# rock-climbing-timer.net
KiCad netlist of a schematic drawn in EAGLE
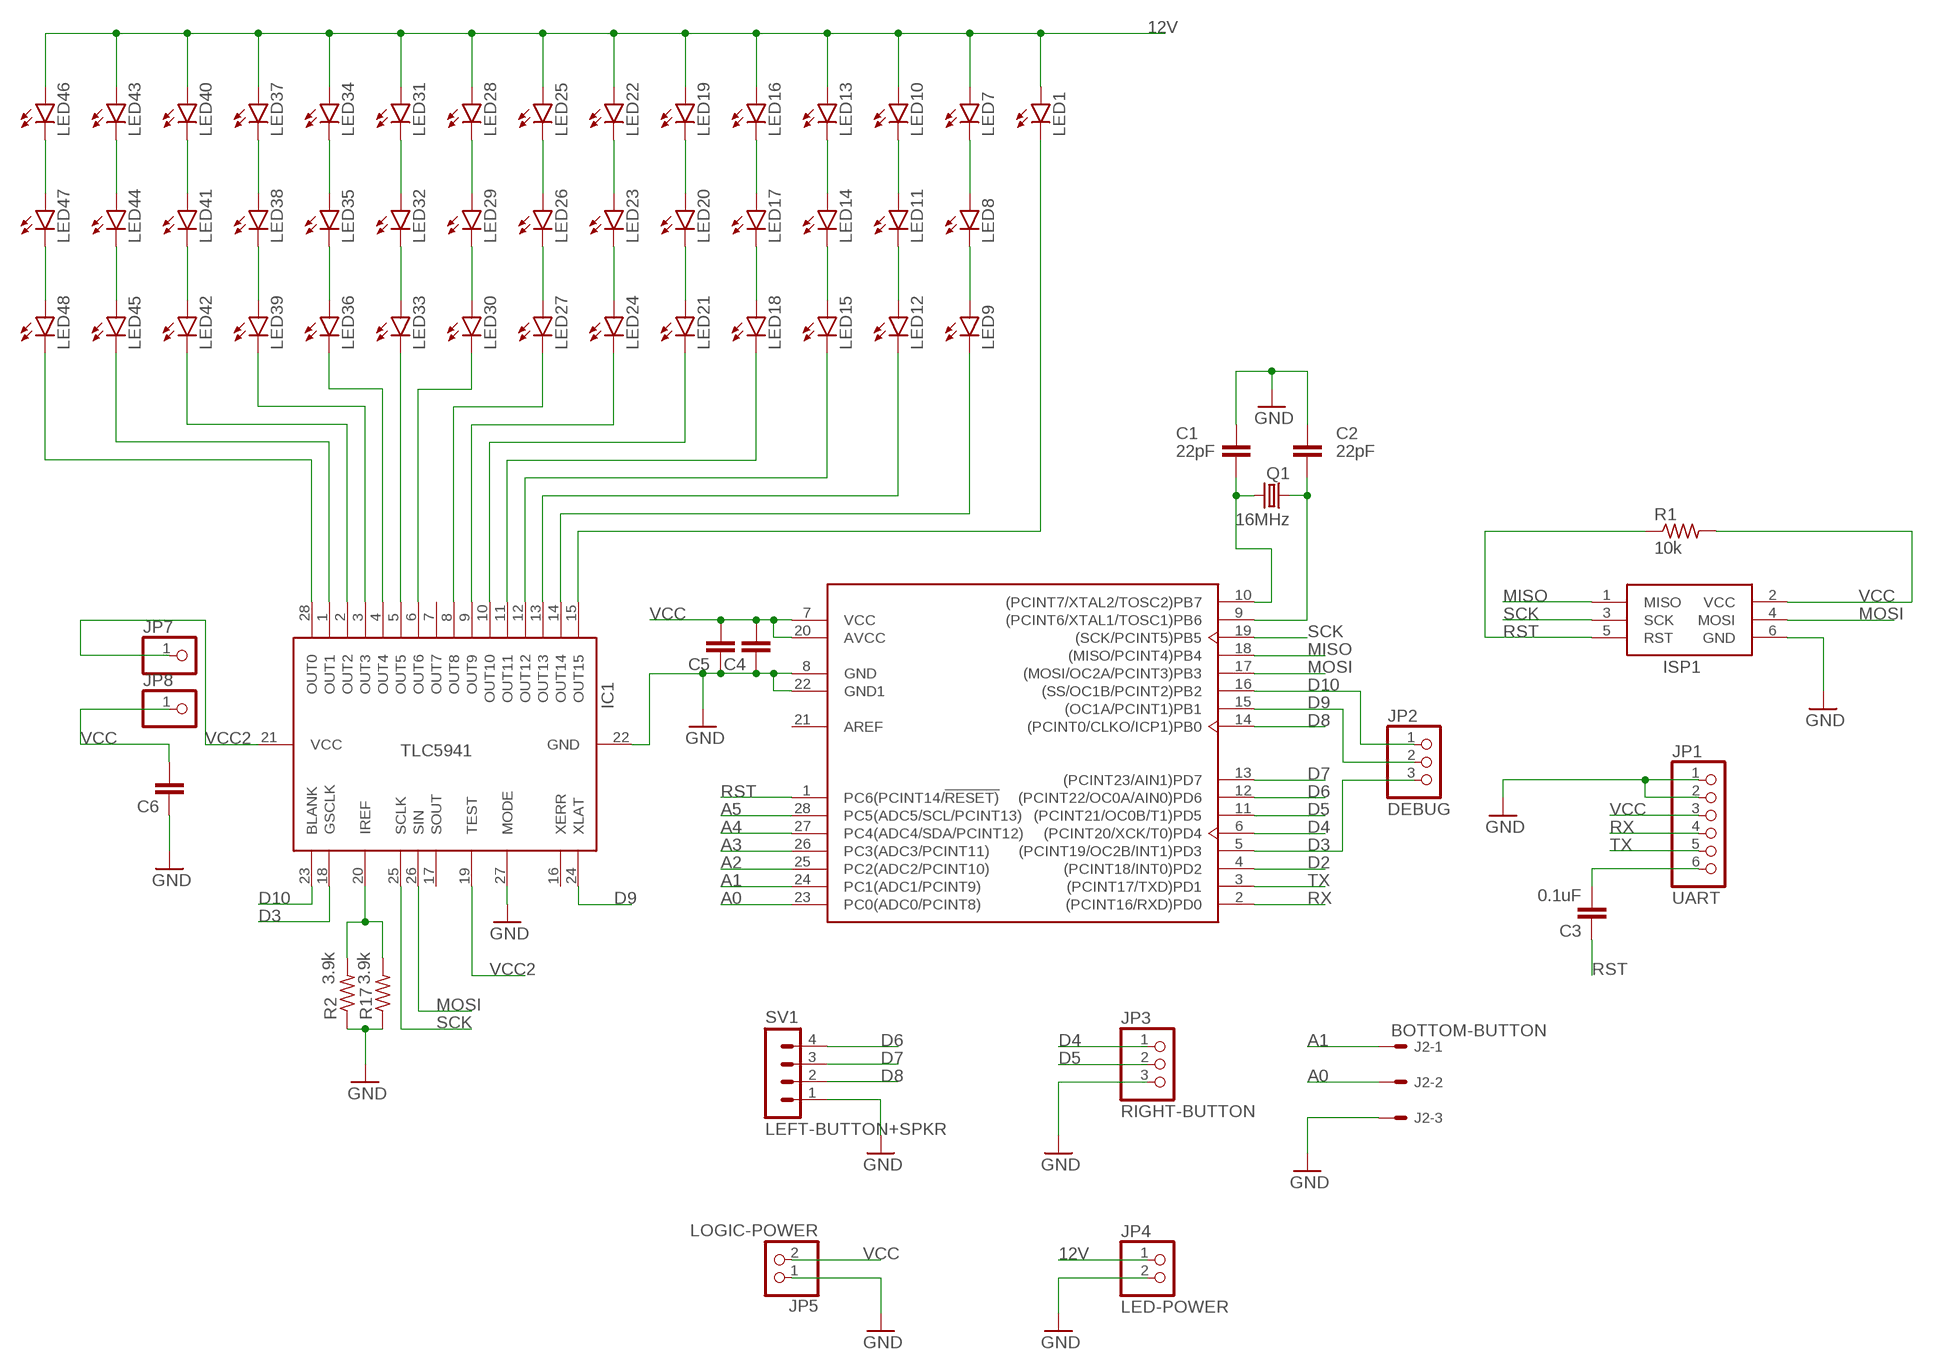
[diagram p0: schematic, sheet 1]

(export (version "E")
  (design (tool "Eeschema 10.0.6"))
  (components
    (comp (ref "C1")
      (value "22pF")
      (footprint "eagle-import:C5B2.5")
      (libsource (lib "eagle-import") (part "C5/2.5"))
    )
    (comp (ref "C2")
      (value "22pF")
      (footprint "eagle-import:C5B2.5")
      (libsource (lib "eagle-import") (part "C5/2.5"))
    )
    (comp (ref "C3")
      (value "0.1uF")
      (footprint "eagle-import:C5B2.5")
      (libsource (lib "eagle-import") (part "C5/2.5"))
    )
    (comp (ref "C4")
      (value "C5/2.5")
      (footprint "eagle-import:C5B2.5")
      (libsource (lib "eagle-import") (part "C5/2.5"))
    )
    (comp (ref "C5")
      (value "C5/2.5")
      (footprint "eagle-import:C5B2.5")
      (libsource (lib "eagle-import") (part "C5/2.5"))
    )
    (comp (ref "C6")
      (value "C5/2.5")
      (footprint "eagle-import:C5B2.5")
      (libsource (lib "eagle-import") (part "C5/2.5"))
    )
    (comp (ref "IC1")
      (value "TLC5941NT")
      (footprint "eagle-import:DIL28-3")
      (libsource (lib "eagle-import") (part "TLC5941NT"))
    )
    (comp (ref "ISP1")
      (value "AVRISP-6")
      (footprint "eagle-import:AVRISP")
      (libsource (lib "eagle-import") (part "AVRISP-6"))
    )
    (comp (ref "J2")
      (value "BOTTOM-BUTTON")
      (footprint "eagle-import:6410-03")
      (fields (field (name "MF") "MOLEX"))
      (libsource (lib "eagle-import") (part "22-?-0327-2031"))
    )
    (comp (ref "JP1")
      (value "UART")
      (footprint "eagle-import:1X06")
      (libsource (lib "eagle-import") (part "PINHD-1X6"))
    )
    (comp (ref "JP2")
      (value "DEBUG")
      (footprint "eagle-import:1X03")
      (libsource (lib "eagle-import") (part "PINHD-1X3"))
    )
    (comp (ref "JP3")
      (value "RIGHT-BUTTON")
      (footprint "eagle-import:1X03")
      (libsource (lib "eagle-import") (part "PINHD-1X3"))
    )
    (comp (ref "JP4")
      (value "LED-POWER")
      (footprint "eagle-import:1X02")
      (libsource (lib "eagle-import") (part "PINHD-1X2"))
    )
    (comp (ref "JP5")
      (value "LOGIC-POWER")
      (footprint "eagle-import:1X02")
      (libsource (lib "eagle-import") (part "PINHD-1X2"))
    )
    (comp (ref "JP7")
      (value "PINHD-1X1CB")
      (footprint "eagle-import:1X01-CLEANBIG")
      (libsource (lib "eagle-import") (part "PINHD-1X1CB"))
    )
    (comp (ref "JP8")
      (value "PINHD-1X1CB")
      (footprint "eagle-import:1X01-CLEANBIG")
      (libsource (lib "eagle-import") (part "PINHD-1X1CB"))
    )
    (comp (ref "LED1")
      (value "LED5MM")
      (footprint "eagle-import:LED5MM")
      (libsource (lib "eagle-import") (part "LED5MM"))
    )
    (comp (ref "LED7")
      (value "LED5MM")
      (footprint "eagle-import:LED5MM")
      (libsource (lib "eagle-import") (part "LED5MM"))
    )
    (comp (ref "LED8")
      (value "LED5MM")
      (footprint "eagle-import:LED5MM")
      (libsource (lib "eagle-import") (part "LED5MM"))
    )
    (comp (ref "LED9")
      (value "LED5MM")
      (footprint "eagle-import:LED5MM")
      (libsource (lib "eagle-import") (part "LED5MM"))
    )
    (comp (ref "LED10")
      (value "LED5MM")
      (footprint "eagle-import:LED5MM")
      (libsource (lib "eagle-import") (part "LED5MM"))
    )
    (comp (ref "LED11")
      (value "LED5MM")
      (footprint "eagle-import:LED5MM")
      (libsource (lib "eagle-import") (part "LED5MM"))
    )
    (comp (ref "LED12")
      (value "LED5MM")
      (footprint "eagle-import:LED5MM")
      (libsource (lib "eagle-import") (part "LED5MM"))
    )
    (comp (ref "LED13")
      (value "LED5MM")
      (footprint "eagle-import:LED5MM")
      (libsource (lib "eagle-import") (part "LED5MM"))
    )
    (comp (ref "LED14")
      (value "LED5MM")
      (footprint "eagle-import:LED5MM")
      (libsource (lib "eagle-import") (part "LED5MM"))
    )
    (comp (ref "LED15")
      (value "LED5MM")
      (footprint "eagle-import:LED5MM")
      (libsource (lib "eagle-import") (part "LED5MM"))
    )
    (comp (ref "LED16")
      (value "LED5MM")
      (footprint "eagle-import:LED5MM")
      (libsource (lib "eagle-import") (part "LED5MM"))
    )
    (comp (ref "LED17")
      (value "LED5MM")
      (footprint "eagle-import:LED5MM")
      (libsource (lib "eagle-import") (part "LED5MM"))
    )
    (comp (ref "LED18")
      (value "LED5MM")
      (footprint "eagle-import:LED5MM")
      (libsource (lib "eagle-import") (part "LED5MM"))
    )
    (comp (ref "LED19")
      (value "LED5MM")
      (footprint "eagle-import:LED5MM")
      (libsource (lib "eagle-import") (part "LED5MM"))
    )
    (comp (ref "LED20")
      (value "LED5MM")
      (footprint "eagle-import:LED5MM")
      (libsource (lib "eagle-import") (part "LED5MM"))
    )
    (comp (ref "LED21")
      (value "LED5MM")
      (footprint "eagle-import:LED5MM")
      (libsource (lib "eagle-import") (part "LED5MM"))
    )
    (comp (ref "LED22")
      (value "LED5MM")
      (footprint "eagle-import:LED5MM")
      (libsource (lib "eagle-import") (part "LED5MM"))
    )
    (comp (ref "LED23")
      (value "LED5MM")
      (footprint "eagle-import:LED5MM")
      (libsource (lib "eagle-import") (part "LED5MM"))
    )
    (comp (ref "LED24")
      (value "LED5MM")
      (footprint "eagle-import:LED5MM")
      (libsource (lib "eagle-import") (part "LED5MM"))
    )
    (comp (ref "LED25")
      (value "LED5MM")
      (footprint "eagle-import:LED5MM")
      (libsource (lib "eagle-import") (part "LED5MM"))
    )
    (comp (ref "LED26")
      (value "LED5MM")
      (footprint "eagle-import:LED5MM")
      (libsource (lib "eagle-import") (part "LED5MM"))
    )
    (comp (ref "LED27")
      (value "LED5MM")
      (footprint "eagle-import:LED5MM")
      (libsource (lib "eagle-import") (part "LED5MM"))
    )
    (comp (ref "LED28")
      (value "LED5MM")
      (footprint "eagle-import:LED5MM")
      (libsource (lib "eagle-import") (part "LED5MM"))
    )
    (comp (ref "LED29")
      (value "LED5MM")
      (footprint "eagle-import:LED5MM")
      (libsource (lib "eagle-import") (part "LED5MM"))
    )
    (comp (ref "LED30")
      (value "LED5MM")
      (footprint "eagle-import:LED5MM")
      (libsource (lib "eagle-import") (part "LED5MM"))
    )
    (comp (ref "LED31")
      (value "LED5MM")
      (footprint "eagle-import:LED5MM")
      (libsource (lib "eagle-import") (part "LED5MM"))
    )
    (comp (ref "LED32")
      (value "LED5MM")
      (footprint "eagle-import:LED5MM")
      (libsource (lib "eagle-import") (part "LED5MM"))
    )
    (comp (ref "LED33")
      (value "LED5MM")
      (footprint "eagle-import:LED5MM")
      (libsource (lib "eagle-import") (part "LED5MM"))
    )
    (comp (ref "LED34")
      (value "LED5MM")
      (footprint "eagle-import:LED5MM")
      (libsource (lib "eagle-import") (part "LED5MM"))
    )
    (comp (ref "LED35")
      (value "LED5MM")
      (footprint "eagle-import:LED5MM")
      (libsource (lib "eagle-import") (part "LED5MM"))
    )
    (comp (ref "LED36")
      (value "LED5MM")
      (footprint "eagle-import:LED5MM")
      (libsource (lib "eagle-import") (part "LED5MM"))
    )
    (comp (ref "LED37")
      (value "LED5MM")
      (footprint "eagle-import:LED5MM")
      (libsource (lib "eagle-import") (part "LED5MM"))
    )
    (comp (ref "LED38")
      (value "LED5MM")
      (footprint "eagle-import:LED5MM")
      (libsource (lib "eagle-import") (part "LED5MM"))
    )
    (comp (ref "LED39")
      (value "LED5MM")
      (footprint "eagle-import:LED5MM")
      (libsource (lib "eagle-import") (part "LED5MM"))
    )
    (comp (ref "LED40")
      (value "LED5MM")
      (footprint "eagle-import:LED5MM")
      (libsource (lib "eagle-import") (part "LED5MM"))
    )
    (comp (ref "LED41")
      (value "LED5MM")
      (footprint "eagle-import:LED5MM")
      (libsource (lib "eagle-import") (part "LED5MM"))
    )
    (comp (ref "LED42")
      (value "LED5MM")
      (footprint "eagle-import:LED5MM")
      (libsource (lib "eagle-import") (part "LED5MM"))
    )
    (comp (ref "LED43")
      (value "LED5MM")
      (footprint "eagle-import:LED5MM")
      (libsource (lib "eagle-import") (part "LED5MM"))
    )
    (comp (ref "LED44")
      (value "LED5MM")
      (footprint "eagle-import:LED5MM")
      (libsource (lib "eagle-import") (part "LED5MM"))
    )
    (comp (ref "LED45")
      (value "LED5MM")
      (footprint "eagle-import:LED5MM")
      (libsource (lib "eagle-import") (part "LED5MM"))
    )
    (comp (ref "LED46")
      (value "LED5MM")
      (footprint "eagle-import:LED5MM")
      (libsource (lib "eagle-import") (part "LED5MM"))
    )
    (comp (ref "LED47")
      (value "LED5MM")
      (footprint "eagle-import:LED5MM")
      (libsource (lib "eagle-import") (part "LED5MM"))
    )
    (comp (ref "LED48")
      (value "LED5MM")
      (footprint "eagle-import:LED5MM")
      (libsource (lib "eagle-import") (part "LED5MM"))
    )
    (comp (ref "Q1")
      (value "16MHz")
      (footprint "eagle-import:HC49_S")
      (libsource (lib "eagle-import") (part "CRYSTALHC49S"))
    )
    (comp (ref "R1")
      (value "10k")
      (footprint "eagle-import:0207_10")
      (libsource (lib "eagle-import") (part "R-US_0207/10"))
    )
    (comp (ref "R2")
      (value "3.9k")
      (footprint "eagle-import:0207_10")
      (libsource (lib "eagle-import") (part "R-US_0207/10"))
    )
    (comp (ref "R17")
      (value "3.9k")
      (footprint "eagle-import:0207_10")
      (libsource (lib "eagle-import") (part "R-US_0207/10"))
    )
    (comp (ref "SV1")
      (value "LEFT-BUTTON+SPKR")
      (footprint "eagle-import:MA04-1")
      (libsource (lib "eagle-import") (part "MA04-1"))
    )
    (comp (ref "U1")
      (value "ATMEGA328P-PU")
      (footprint "eagle-import:DIP-28")
      (fields
        (field (name "DIGIKEY_PART_NUMBER") "ATMEGA328P-PU-ND")
        (field (name "MANUFACTURER") "Microchip Technology")
        (field (name "CREATED_BY") "PCBLayout.com")
      )
      (libsource (lib "eagle-import") (part "ATMEGA328P-PU"))
    )
  )
  (nets
    (net (code "1") (name "/12V") (class "Default")
      (node (ref "JP4") (pin "1") (pinfunction "1_1") (pintype "passive"))
      (node (ref "LED1") (pin "A") (pinfunction "A_A") (pintype "passive"))
      (node (ref "LED10") (pin "A") (pinfunction "A_A") (pintype "passive"))
      (node (ref "LED13") (pin "A") (pinfunction "A_A") (pintype "passive"))
      (node (ref "LED16") (pin "A") (pinfunction "A_A") (pintype "passive"))
      (node (ref "LED19") (pin "A") (pinfunction "A_A") (pintype "passive"))
      (node (ref "LED22") (pin "A") (pinfunction "A_A") (pintype "passive"))
      (node (ref "LED25") (pin "A") (pinfunction "A_A") (pintype "passive"))
      (node (ref "LED28") (pin "A") (pinfunction "A_A") (pintype "passive"))
      (node (ref "LED31") (pin "A") (pinfunction "A_A") (pintype "passive"))
      (node (ref "LED34") (pin "A") (pinfunction "A_A") (pintype "passive"))
      (node (ref "LED37") (pin "A") (pinfunction "A_A") (pintype "passive"))
      (node (ref "LED40") (pin "A") (pinfunction "A_A") (pintype "passive"))
      (node (ref "LED43") (pin "A") (pinfunction "A_A") (pintype "passive"))
      (node (ref "LED46") (pin "A") (pinfunction "A_A") (pintype "passive"))
      (node (ref "LED7") (pin "A") (pinfunction "A_A") (pintype "passive"))
    )
    (net (code "2") (name "/A0") (class "Default")
      (node (ref "J2") (pin "2") (pinfunction "S_2") (pintype "passive"))
      (node (ref "U1") (pin "23") (pinfunction "PC0(ADC0/PCINT8)_23") (pintype "bidirectional"))
    )
    (net (code "3") (name "/A1") (class "Default")
      (node (ref "J2") (pin "1") (pinfunction "S_1") (pintype "passive"))
      (node (ref "U1") (pin "24") (pinfunction "PC1(ADC1/PCINT9)_24") (pintype "bidirectional"))
    )
    (net (code "4") (name "/A2") (class "Default")
      (node (ref "U1") (pin "25") (pinfunction "PC2(ADC2/PCINT10)_25") (pintype "bidirectional"))
    )
    (net (code "5") (name "/A3") (class "Default")
      (node (ref "U1") (pin "26") (pinfunction "PC3(ADC3/PCINT11)_26") (pintype "bidirectional"))
    )
    (net (code "6") (name "/A4") (class "Default")
      (node (ref "U1") (pin "27") (pinfunction "PC4(ADC4/SDA/PCINT12)_27") (pintype "bidirectional"))
    )
    (net (code "7") (name "/A5") (class "Default")
      (node (ref "U1") (pin "28") (pinfunction "PC5(ADC5/SCL/PCINT13)_28") (pintype "bidirectional"))
    )
    (net (code "8") (name "/D2") (class "Default")
      (node (ref "U1") (pin "4") (pinfunction "(PCINT18/INT0)PD2_4") (pintype "bidirectional"))
    )
    (net (code "9") (name "/D3") (class "Default")
      (node (ref "IC1") (pin "18") (pinfunction "GSCLK_18") (pintype "input"))
      (node (ref "JP2") (pin "3") (pinfunction "3_3") (pintype "passive"))
      (node (ref "U1") (pin "5") (pinfunction "(PCINT19/OC2B/INT1)PD3_5") (pintype "bidirectional"))
    )
    (net (code "10") (name "/D4") (class "Default")
      (node (ref "JP3") (pin "1") (pinfunction "1_1") (pintype "passive"))
      (node (ref "U1") (pin "6") (pinfunction "(PCINT20/XCK/T0)PD4_6") (pintype "bidirectional"))
    )
    (net (code "11") (name "/D5") (class "Default")
      (node (ref "JP3") (pin "2") (pinfunction "2_2") (pintype "passive"))
      (node (ref "U1") (pin "11") (pinfunction "(PCINT21/OC0B/T1)PD5_11") (pintype "bidirectional"))
    )
    (net (code "12") (name "/D6") (class "Default")
      (node (ref "SV1") (pin "4") (pinfunction "4_4") (pintype "passive"))
      (node (ref "U1") (pin "12") (pinfunction "(PCINT22/OC0A/AIN0)PD6_12") (pintype "bidirectional"))
    )
    (net (code "13") (name "/D7") (class "Default")
      (node (ref "SV1") (pin "3") (pinfunction "3_3") (pintype "passive"))
      (node (ref "U1") (pin "13") (pinfunction "(PCINT23/AIN1)PD7_13") (pintype "bidirectional"))
    )
    (net (code "14") (name "/D8") (class "Default")
      (node (ref "SV1") (pin "2") (pinfunction "2_2") (pintype "passive"))
      (node (ref "U1") (pin "14") (pinfunction "(PCINT0/CLKO/ICP1)PB0_14") (pintype "bidirectional"))
    )
    (net (code "15") (name "/D9") (class "Default")
      (node (ref "IC1") (pin "24") (pinfunction "XLAT_24") (pintype "input"))
      (node (ref "JP2") (pin "2") (pinfunction "2_2") (pintype "passive"))
      (node (ref "U1") (pin "15") (pinfunction "(OC1A/PCINT1)PB1_15") (pintype "bidirectional"))
    )
    (net (code "16") (name "/D10") (class "Default")
      (node (ref "IC1") (pin "23") (pinfunction "BLANK_23") (pintype "input"))
      (node (ref "JP2") (pin "1") (pinfunction "1_1") (pintype "passive"))
      (node (ref "U1") (pin "16") (pinfunction "(SS/OC1B/PCINT2)PB2_16") (pintype "bidirectional"))
    )
    (net (code "17") (name "/MISO") (class "Default")
      (node (ref "ISP1") (pin "1") (pinfunction "MISO_1") (pintype "input"))
      (node (ref "U1") (pin "18") (pinfunction "(MISO/PCINT4)PB4_18") (pintype "bidirectional"))
    )
    (net (code "18") (name "/MOSI") (class "Default")
      (node (ref "IC1") (pin "26") (pinfunction "SIN_26") (pintype "input"))
      (node (ref "ISP1") (pin "4") (pinfunction "MOSI_4") (pintype "output"))
      (node (ref "U1") (pin "17") (pinfunction "(MOSI/OC2A/PCINT3)PB3_17") (pintype "bidirectional"))
    )
    (net (code "19") (name "/RST") (class "Default")
      (node (ref "C3") (pin "1") (pinfunction "1_1") (pintype "passive"))
      (node (ref "ISP1") (pin "5") (pinfunction "RST_5") (pintype "output"))
      (node (ref "R1") (pin "1") (pinfunction "1_1") (pintype "passive"))
      (node (ref "U1") (pin "1") (pinfunction "PC6(PCINT14/~{RESET})_1") (pintype "bidirectional"))
    )
    (net (code "20") (name "/RX") (class "Default")
      (node (ref "JP1") (pin "4") (pinfunction "4_4") (pintype "passive"))
      (node (ref "U1") (pin "2") (pinfunction "(PCINT16/RXD)PD0_2") (pintype "bidirectional"))
    )
    (net (code "21") (name "/SCK") (class "Default")
      (node (ref "IC1") (pin "25") (pinfunction "SCLK_25") (pintype "input"))
      (node (ref "ISP1") (pin "3") (pinfunction "SCK_3") (pintype "output"))
      (node (ref "U1") (pin "19") (pinfunction "(SCK/PCINT5)PB5_19") (pintype "bidirectional"))
    )
    (net (code "22") (name "/TX") (class "Default")
      (node (ref "JP1") (pin "5") (pinfunction "5_5") (pintype "passive"))
      (node (ref "U1") (pin "3") (pinfunction "(PCINT17/TXD)PD1_3") (pintype "bidirectional"))
    )
    (net (code "23") (name "/VCC") (class "Default")
      (node (ref "C4") (pin "2") (pinfunction "2_2") (pintype "passive"))
      (node (ref "C5") (pin "2") (pinfunction "2_2") (pintype "passive"))
      (node (ref "C6") (pin "2") (pinfunction "2_2") (pintype "passive"))
      (node (ref "ISP1") (pin "2") (pinfunction "VCC_2") (pintype "power_in"))
      (node (ref "JP1") (pin "3") (pinfunction "3_3") (pintype "passive"))
      (node (ref "JP5") (pin "2") (pinfunction "2_2") (pintype "passive"))
      (node (ref "JP8") (pin "1") (pinfunction "1_1") (pintype "passive"))
      (node (ref "R1") (pin "2") (pinfunction "2_2") (pintype "passive"))
      (node (ref "U1") (pin "20") (pinfunction "AVCC_20") (pintype "power_in"))
      (node (ref "U1") (pin "7") (pinfunction "VCC_7") (pintype "power_in"))
    )
    (net (code "24") (name "/VCC2") (class "Default")
      (node (ref "IC1") (pin "19") (pinfunction "TEST_19") (pintype "input"))
      (node (ref "IC1") (pin "21") (pinfunction "VCC_21") (pintype "power_in"))
      (node (ref "JP7") (pin "1") (pinfunction "1_1") (pintype "passive"))
    )
    (net (code "25") (name "GND") (class "Default")
      (node (ref "C1") (pin "1") (pinfunction "1_1") (pintype "passive"))
      (node (ref "C2") (pin "1") (pinfunction "1_1") (pintype "passive"))
      (node (ref "C4") (pin "1") (pinfunction "1_1") (pintype "passive"))
      (node (ref "C5") (pin "1") (pinfunction "1_1") (pintype "passive"))
      (node (ref "C6") (pin "1") (pinfunction "1_1") (pintype "passive"))
      (node (ref "IC1") (pin "22") (pinfunction "GND_22") (pintype "power_in"))
      (node (ref "IC1") (pin "27") (pinfunction "MODE_27") (pintype "input"))
      (node (ref "ISP1") (pin "6") (pinfunction "GND_6") (pintype "power_in"))
      (node (ref "J2") (pin "3") (pinfunction "S_3") (pintype "passive"))
      (node (ref "JP1") (pin "1") (pinfunction "1_1") (pintype "passive"))
      (node (ref "JP1") (pin "2") (pinfunction "2_2") (pintype "passive"))
      (node (ref "JP3") (pin "3") (pinfunction "3_3") (pintype "passive"))
      (node (ref "JP4") (pin "2") (pinfunction "2_2") (pintype "passive"))
      (node (ref "JP5") (pin "1") (pinfunction "1_1") (pintype "passive"))
      (node (ref "R17") (pin "1") (pinfunction "1_1") (pintype "passive"))
      (node (ref "R2") (pin "1") (pinfunction "1_1") (pintype "passive"))
      (node (ref "SV1") (pin "1") (pinfunction "1_1") (pintype "passive"))
      (node (ref "U1") (pin "22") (pinfunction "GND1_22") (pintype "power_in"))
      (node (ref "U1") (pin "8") (pinfunction "GND_8") (pintype "power_in"))
    )
    (net (code "26") (name "Net-(C3-Pad2)") (class "Default")
      (node (ref "C3") (pin "2") (pinfunction "2_2") (pintype "passive"))
      (node (ref "JP1") (pin "6") (pinfunction "6_6") (pintype "passive"))
    )
    (net (code "27") (name "Net-(IC1-IREF)") (class "Default")
      (node (ref "IC1") (pin "20") (pinfunction "IREF_20") (pintype "bidirectional"))
      (node (ref "R17") (pin "2") (pinfunction "2_2") (pintype "passive"))
      (node (ref "R2") (pin "2") (pinfunction "2_2") (pintype "passive"))
    )
    (net (code "28") (name "Net-(IC1-OUT0)") (class "Default")
      (node (ref "IC1") (pin "28") (pinfunction "OUT0_28") (pintype "output"))
      (node (ref "LED48") (pin "K") (pinfunction "C_K") (pintype "passive"))
    )
    (net (code "29") (name "Net-(IC1-OUT1)") (class "Default")
      (node (ref "IC1") (pin "1") (pinfunction "OUT1_1") (pintype "output"))
      (node (ref "LED45") (pin "K") (pinfunction "C_K") (pintype "passive"))
    )
    (net (code "30") (name "Net-(IC1-OUT2)") (class "Default")
      (node (ref "IC1") (pin "2") (pinfunction "OUT2_2") (pintype "output"))
      (node (ref "LED42") (pin "K") (pinfunction "C_K") (pintype "passive"))
    )
    (net (code "31") (name "Net-(IC1-OUT3)") (class "Default")
      (node (ref "IC1") (pin "3") (pinfunction "OUT3_3") (pintype "output"))
      (node (ref "LED39") (pin "K") (pinfunction "C_K") (pintype "passive"))
    )
    (net (code "32") (name "Net-(IC1-OUT4)") (class "Default")
      (node (ref "IC1") (pin "4") (pinfunction "OUT4_4") (pintype "output"))
      (node (ref "LED36") (pin "K") (pinfunction "C_K") (pintype "passive"))
    )
    (net (code "33") (name "Net-(IC1-OUT5)") (class "Default")
      (node (ref "IC1") (pin "5") (pinfunction "OUT5_5") (pintype "output"))
      (node (ref "LED33") (pin "K") (pinfunction "C_K") (pintype "passive"))
    )
    (net (code "34") (name "Net-(IC1-OUT6)") (class "Default")
      (node (ref "IC1") (pin "6") (pinfunction "OUT6_6") (pintype "output"))
      (node (ref "LED30") (pin "K") (pinfunction "C_K") (pintype "passive"))
    )
    (net (code "35") (name "Net-(IC1-OUT8)") (class "Default")
      (node (ref "IC1") (pin "8") (pinfunction "OUT8_8") (pintype "output"))
      (node (ref "LED27") (pin "K") (pinfunction "C_K") (pintype "passive"))
    )
    (net (code "36") (name "Net-(IC1-OUT9)") (class "Default")
      (node (ref "IC1") (pin "9") (pinfunction "OUT9_9") (pintype "output"))
      (node (ref "LED24") (pin "K") (pinfunction "C_K") (pintype "passive"))
    )
    (net (code "37") (name "Net-(IC1-OUT10)") (class "Default")
      (node (ref "IC1") (pin "10") (pinfunction "OUT10_10") (pintype "output"))
      (node (ref "LED21") (pin "K") (pinfunction "C_K") (pintype "passive"))
    )
    (net (code "38") (name "Net-(IC1-OUT11)") (class "Default")
      (node (ref "IC1") (pin "11") (pinfunction "OUT11_11") (pintype "output"))
      (node (ref "LED18") (pin "K") (pinfunction "C_K") (pintype "passive"))
    )
    (net (code "39") (name "Net-(IC1-OUT12)") (class "Default")
      (node (ref "IC1") (pin "12") (pinfunction "OUT12_12") (pintype "output"))
      (node (ref "LED15") (pin "K") (pinfunction "C_K") (pintype "passive"))
    )
    (net (code "40") (name "Net-(IC1-OUT13)") (class "Default")
      (node (ref "IC1") (pin "13") (pinfunction "OUT13_13") (pintype "output"))
      (node (ref "LED12") (pin "K") (pinfunction "C_K") (pintype "passive"))
    )
    (net (code "41") (name "Net-(IC1-OUT14)") (class "Default")
      (node (ref "IC1") (pin "14") (pinfunction "OUT14_14") (pintype "output"))
      (node (ref "LED9") (pin "K") (pinfunction "C_K") (pintype "passive"))
    )
    (net (code "42") (name "Net-(IC1-OUT15)") (class "Default")
      (node (ref "IC1") (pin "15") (pinfunction "OUT15_15") (pintype "output"))
      (node (ref "LED1") (pin "K") (pinfunction "C_K") (pintype "passive"))
    )
    (net (code "43") (name "Net-(LED7-C)") (class "Default")
      (node (ref "LED7") (pin "K") (pinfunction "C_K") (pintype "passive"))
      (node (ref "LED8") (pin "A") (pinfunction "A_A") (pintype "passive"))
    )
    (net (code "44") (name "Net-(LED8-C)") (class "Default")
      (node (ref "LED8") (pin "K") (pinfunction "C_K") (pintype "passive"))
      (node (ref "LED9") (pin "A") (pinfunction "A_A") (pintype "passive"))
    )
    (net (code "45") (name "Net-(LED10-C)") (class "Default")
      (node (ref "LED10") (pin "K") (pinfunction "C_K") (pintype "passive"))
      (node (ref "LED11") (pin "A") (pinfunction "A_A") (pintype "passive"))
    )
    (net (code "46") (name "Net-(LED11-C)") (class "Default")
      (node (ref "LED11") (pin "K") (pinfunction "C_K") (pintype "passive"))
      (node (ref "LED12") (pin "A") (pinfunction "A_A") (pintype "passive"))
    )
    (net (code "47") (name "Net-(LED13-C)") (class "Default")
      (node (ref "LED13") (pin "K") (pinfunction "C_K") (pintype "passive"))
      (node (ref "LED14") (pin "A") (pinfunction "A_A") (pintype "passive"))
    )
    (net (code "48") (name "Net-(LED14-C)") (class "Default")
      (node (ref "LED14") (pin "K") (pinfunction "C_K") (pintype "passive"))
      (node (ref "LED15") (pin "A") (pinfunction "A_A") (pintype "passive"))
    )
    (net (code "49") (name "Net-(LED16-C)") (class "Default")
      (node (ref "LED16") (pin "K") (pinfunction "C_K") (pintype "passive"))
      (node (ref "LED17") (pin "A") (pinfunction "A_A") (pintype "passive"))
    )
    (net (code "50") (name "Net-(LED17-C)") (class "Default")
      (node (ref "LED17") (pin "K") (pinfunction "C_K") (pintype "passive"))
      (node (ref "LED18") (pin "A") (pinfunction "A_A") (pintype "passive"))
    )
    (net (code "51") (name "Net-(LED19-C)") (class "Default")
      (node (ref "LED19") (pin "K") (pinfunction "C_K") (pintype "passive"))
      (node (ref "LED20") (pin "A") (pinfunction "A_A") (pintype "passive"))
    )
    (net (code "52") (name "Net-(LED20-C)") (class "Default")
      (node (ref "LED20") (pin "K") (pinfunction "C_K") (pintype "passive"))
      (node (ref "LED21") (pin "A") (pinfunction "A_A") (pintype "passive"))
    )
    (net (code "53") (name "Net-(LED22-C)") (class "Default")
      (node (ref "LED22") (pin "K") (pinfunction "C_K") (pintype "passive"))
      (node (ref "LED23") (pin "A") (pinfunction "A_A") (pintype "passive"))
    )
    (net (code "54") (name "Net-(LED23-C)") (class "Default")
      (node (ref "LED23") (pin "K") (pinfunction "C_K") (pintype "passive"))
      (node (ref "LED24") (pin "A") (pinfunction "A_A") (pintype "passive"))
    )
    (net (code "55") (name "Net-(LED25-C)") (class "Default")
      (node (ref "LED25") (pin "K") (pinfunction "C_K") (pintype "passive"))
      (node (ref "LED26") (pin "A") (pinfunction "A_A") (pintype "passive"))
    )
    (net (code "56") (name "Net-(LED26-C)") (class "Default")
      (node (ref "LED26") (pin "K") (pinfunction "C_K") (pintype "passive"))
      (node (ref "LED27") (pin "A") (pinfunction "A_A") (pintype "passive"))
    )
    (net (code "57") (name "Net-(LED28-C)") (class "Default")
      (node (ref "LED28") (pin "K") (pinfunction "C_K") (pintype "passive"))
      (node (ref "LED29") (pin "A") (pinfunction "A_A") (pintype "passive"))
    )
    (net (code "58") (name "Net-(LED29-C)") (class "Default")
      (node (ref "LED29") (pin "K") (pinfunction "C_K") (pintype "passive"))
      (node (ref "LED30") (pin "A") (pinfunction "A_A") (pintype "passive"))
    )
    (net (code "59") (name "Net-(LED31-C)") (class "Default")
      (node (ref "LED31") (pin "K") (pinfunction "C_K") (pintype "passive"))
      (node (ref "LED32") (pin "A") (pinfunction "A_A") (pintype "passive"))
    )
    (net (code "60") (name "Net-(LED32-C)") (class "Default")
      (node (ref "LED32") (pin "K") (pinfunction "C_K") (pintype "passive"))
      (node (ref "LED33") (pin "A") (pinfunction "A_A") (pintype "passive"))
    )
    (net (code "61") (name "Net-(LED34-C)") (class "Default")
      (node (ref "LED34") (pin "K") (pinfunction "C_K") (pintype "passive"))
      (node (ref "LED35") (pin "A") (pinfunction "A_A") (pintype "passive"))
    )
    (net (code "62") (name "Net-(LED35-C)") (class "Default")
      (node (ref "LED35") (pin "K") (pinfunction "C_K") (pintype "passive"))
      (node (ref "LED36") (pin "A") (pinfunction "A_A") (pintype "passive"))
    )
    (net (code "63") (name "Net-(LED37-C)") (class "Default")
      (node (ref "LED37") (pin "K") (pinfunction "C_K") (pintype "passive"))
      (node (ref "LED38") (pin "A") (pinfunction "A_A") (pintype "passive"))
    )
    (net (code "64") (name "Net-(LED38-C)") (class "Default")
      (node (ref "LED38") (pin "K") (pinfunction "C_K") (pintype "passive"))
      (node (ref "LED39") (pin "A") (pinfunction "A_A") (pintype "passive"))
    )
    (net (code "65") (name "Net-(LED40-C)") (class "Default")
      (node (ref "LED40") (pin "K") (pinfunction "C_K") (pintype "passive"))
      (node (ref "LED41") (pin "A") (pinfunction "A_A") (pintype "passive"))
    )
    (net (code "66") (name "Net-(LED41-C)") (class "Default")
      (node (ref "LED41") (pin "K") (pinfunction "C_K") (pintype "passive"))
      (node (ref "LED42") (pin "A") (pinfunction "A_A") (pintype "passive"))
    )
    (net (code "67") (name "Net-(LED43-C)") (class "Default")
      (node (ref "LED43") (pin "K") (pinfunction "C_K") (pintype "passive"))
      (node (ref "LED44") (pin "A") (pinfunction "A_A") (pintype "passive"))
    )
    (net (code "68") (name "Net-(LED44-C)") (class "Default")
      (node (ref "LED44") (pin "K") (pinfunction "C_K") (pintype "passive"))
      (node (ref "LED45") (pin "A") (pinfunction "A_A") (pintype "passive"))
    )
    (net (code "69") (name "Net-(LED46-C)") (class "Default")
      (node (ref "LED46") (pin "K") (pinfunction "C_K") (pintype "passive"))
      (node (ref "LED47") (pin "A") (pinfunction "A_A") (pintype "passive"))
    )
    (net (code "70") (name "Net-(LED47-C)") (class "Default")
      (node (ref "LED47") (pin "K") (pinfunction "C_K") (pintype "passive"))
      (node (ref "LED48") (pin "A") (pinfunction "A_A") (pintype "passive"))
    )
    (net (code "71") (name "Net-(U1-(PCINT6{slash}XTAL1{slash}TOSC1)PB6)") (class "Default")
      (node (ref "C2") (pin "2") (pinfunction "2_2") (pintype "passive"))
      (node (ref "Q1") (pin "1") (pinfunction "1_1") (pintype "passive"))
      (node (ref "U1") (pin "9") (pinfunction "(PCINT6/XTAL1/TOSC1)PB6_9") (pintype "bidirectional"))
    )
    (net (code "72") (name "Net-(U1-(PCINT7{slash}XTAL2{slash}TOSC2)PB7)") (class "Default")
      (node (ref "C1") (pin "2") (pinfunction "2_2") (pintype "passive"))
      (node (ref "Q1") (pin "2") (pinfunction "2_2") (pintype "passive"))
      (node (ref "U1") (pin "10") (pinfunction "(PCINT7/XTAL2/TOSC2)PB7_10") (pintype "bidirectional"))
    )
    (net (code "73") (name "unconnected-(IC1-OUT7-Pad7)") (class "Default")
      (node (ref "IC1") (pin "7") (pinfunction "OUT7_7") (pintype "output"))
    )
    (net (code "74") (name "unconnected-(IC1-SOUT-Pad17)") (class "Default")
      (node (ref "IC1") (pin "17") (pinfunction "SOUT_17") (pintype "output"))
    )
    (net (code "75") (name "unconnected-(IC1-XERR-Pad16)") (class "Default")
      (node (ref "IC1") (pin "16") (pinfunction "XERR_16") (pintype "output"))
    )
    (net (code "76") (name "unconnected-(U1-AREF-Pad21)") (class "Default")
      (node (ref "U1") (pin "21") (pinfunction "AREF_21") (pintype "input"))
    )
  )
)
